# RS232_2xNPN_DTR.net
KiCad netlist of a schematic drawn in EAGLE
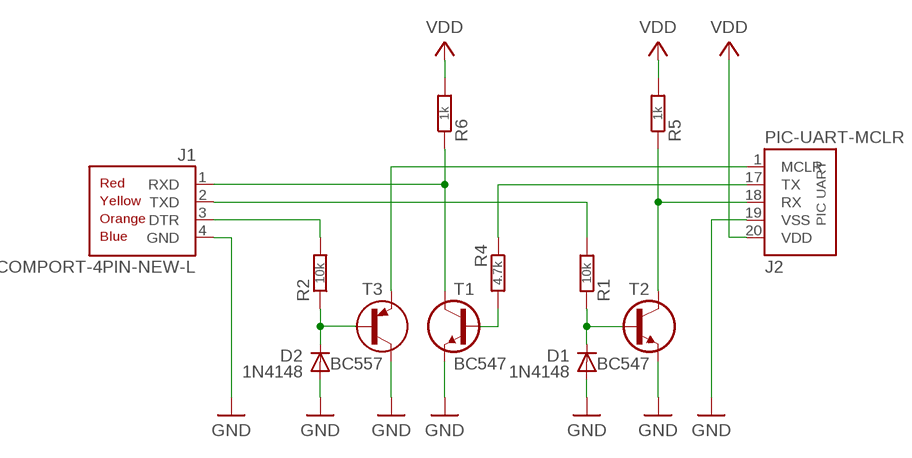
[diagram p0: schematic, sheet 1]

(export (version "E")
  (design (tool "Eeschema 10.0.6"))
  (components
    (comp (ref "D1")
      (value "1N4148")
      (footprint "eagle-import:DO34-2,5-A")
      (libsource (lib "eagle-import") (part "1N414834-2,5-A"))
    )
    (comp (ref "D2")
      (value "1N4148")
      (footprint "eagle-import:DO34-2,5-A")
      (libsource (lib "eagle-import") (part "1N414834-2,5-A"))
    )
    (comp (ref "J1")
      (value "COMPORT-4PIN-NEW-L")
      (footprint "eagle-import:RS232-4PIN-NEW-L")
      (libsource (lib "eagle-import") (part "COMPORT-4PIN-NEW-L"))
    )
    (comp (ref "J2")
      (value "PIC-UART-MCLR")
      (footprint "eagle-import:PIC-UART-MCLR")
      (libsource (lib "eagle-import") (part "PIC-UART-MCLR"))
    )
    (comp (ref "R1")
      (value "10k")
      (footprint "eagle-import:0202_7")
      (libsource (lib "eagle-import") (part "R0202/7"))
    )
    (comp (ref "R2")
      (value "10k")
      (footprint "eagle-import:0202_10")
      (libsource (lib "eagle-import") (part "R0202/10"))
    )
    (comp (ref "R4")
      (value "4.7k")
      (footprint "eagle-import:0202_7-V")
      (libsource (lib "eagle-import") (part "R0202/7-V"))
    )
    (comp (ref "R5")
      (value "1k")
      (footprint "eagle-import:0202_5-V")
      (libsource (lib "eagle-import") (part "R0202/5-V"))
    )
    (comp (ref "R6")
      (value "1k")
      (footprint "eagle-import:0202_5-V")
      (libsource (lib "eagle-import") (part "R0202/5-V"))
    )
    (comp (ref "T1")
      (value "BC547")
      (footprint "eagle-import:TO92-CBE")
      (libsource (lib "eagle-import") (part "BC547CBE"))
    )
    (comp (ref "T2")
      (value "BC547")
      (footprint "eagle-import:TO92-CBE")
      (libsource (lib "eagle-import") (part "BC547CBE"))
    )
    (comp (ref "T3")
      (value "BC557")
      (footprint "eagle-import:TO92-CBE")
      (libsource (lib "eagle-import") (part "BC557CBE"))
    )
  )
  (nets
    (net (code "1") (name "GND") (class "Default")
      (node (ref "D1") (pin "A") (pinfunction "A_A") (pintype "passive"))
      (node (ref "D2") (pin "A") (pinfunction "A_A") (pintype "passive"))
      (node (ref "J1") (pin "4") (pinfunction "GND_4") (pintype "passive"))
      (node (ref "J2") (pin "19") (pinfunction "VSS_19") (pintype "passive"))
      (node (ref "T1") (pin "E") (pinfunction "E_E") (pintype "passive"))
      (node (ref "T2") (pin "E") (pinfunction "E_E") (pintype "passive"))
      (node (ref "T3") (pin "C") (pinfunction "C_C") (pintype "passive"))
    )
    (net (code "2") (name "Net-(D1-PadC)") (class "Default")
      (node (ref "D1") (pin "C") (pinfunction "C_C") (pintype "passive"))
      (node (ref "R1") (pin "1") (pinfunction "1_1") (pintype "passive"))
      (node (ref "T2") (pin "B") (pinfunction "B_B") (pintype "passive"))
    )
    (net (code "3") (name "Net-(D2-PadC)") (class "Default")
      (node (ref "D2") (pin "C") (pinfunction "C_C") (pintype "passive"))
      (node (ref "R2") (pin "1") (pinfunction "1_1") (pintype "passive"))
      (node (ref "T3") (pin "B") (pinfunction "B_B") (pintype "passive"))
    )
    (net (code "4") (name "Net-(J1-DTR)") (class "Default")
      (node (ref "J1") (pin "3") (pinfunction "DTR_3") (pintype "passive"))
      (node (ref "R2") (pin "2") (pinfunction "2_2") (pintype "passive"))
    )
    (net (code "5") (name "Net-(J1-RXD)") (class "Default")
      (node (ref "J1") (pin "1") (pinfunction "RXD_1") (pintype "passive"))
      (node (ref "R6") (pin "1") (pinfunction "1_1") (pintype "passive"))
      (node (ref "T1") (pin "C") (pinfunction "C_C") (pintype "passive"))
    )
    (net (code "6") (name "Net-(J1-TXD)") (class "Default")
      (node (ref "J1") (pin "2") (pinfunction "TXD_2") (pintype "passive"))
      (node (ref "R1") (pin "2") (pinfunction "2_2") (pintype "passive"))
    )
    (net (code "7") (name "Net-(J2-MCLR)") (class "Default")
      (node (ref "J2") (pin "1") (pinfunction "MCLR_1") (pintype "passive"))
      (node (ref "T3") (pin "E") (pinfunction "E_E") (pintype "passive"))
    )
    (net (code "8") (name "Net-(J2-RX)") (class "Default")
      (node (ref "J2") (pin "18") (pinfunction "RX_18") (pintype "passive"))
      (node (ref "R5") (pin "1") (pinfunction "1_1") (pintype "passive"))
      (node (ref "T2") (pin "C") (pinfunction "C_C") (pintype "passive"))
    )
    (net (code "9") (name "Net-(J2-TX)") (class "Default")
      (node (ref "J2") (pin "17") (pinfunction "TX_17") (pintype "passive"))
      (node (ref "R4") (pin "1") (pinfunction "1_1") (pintype "passive"))
    )
    (net (code "10") (name "Net-(R4-Pad2)") (class "Default")
      (node (ref "R4") (pin "2") (pinfunction "2_2") (pintype "passive"))
      (node (ref "T1") (pin "B") (pinfunction "B_B") (pintype "passive"))
    )
    (net (code "11") (name "VDD") (class "Default")
      (node (ref "J2") (pin "20") (pinfunction "VDD_20") (pintype "passive"))
      (node (ref "R5") (pin "2") (pinfunction "2_2") (pintype "passive"))
      (node (ref "R6") (pin "2") (pinfunction "2_2") (pintype "passive"))
    )
  )
)
